# SimpleTimerPCB.net
KiCad netlist of a schematic drawn in EAGLE
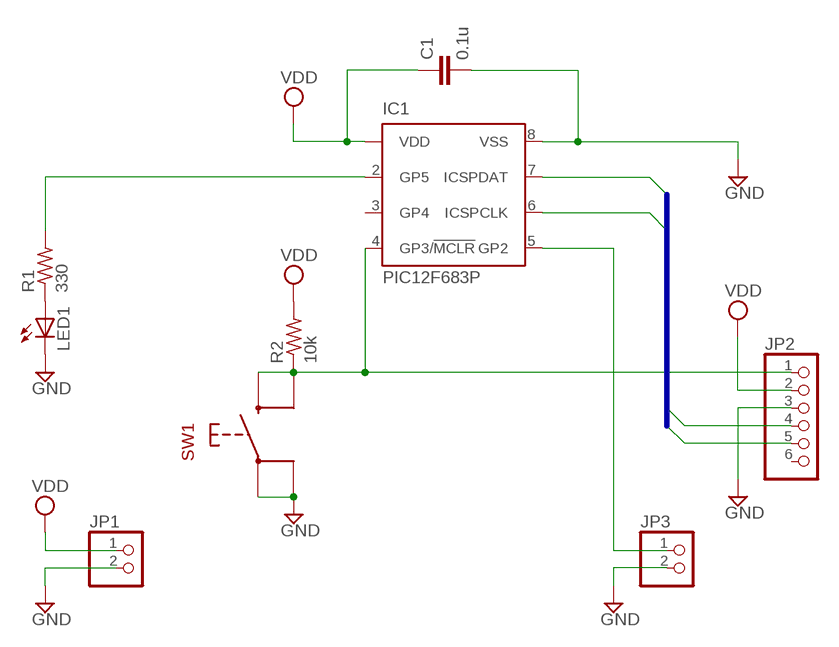
[diagram p0: schematic, sheet 1]

(export (version "E")
  (design (tool "Eeschema 10.0.6"))
  (components
    (comp (ref "C1")
      (value "0.1u")
      (footprint "eagle-import:C050-024X044")
      (libsource (lib "eagle-import") (part "C-EU050-024X044"))
    )
    (comp (ref "IC1")
      (value "PIC12F683P")
      (footprint "eagle-import:DIL8")
      (fields (field (name "MF") "MICROCHIP") (field (name "MPN") "PIC12F683-I/P"))
      (libsource (lib "eagle-import") (part "PIC12F683P"))
    )
    (comp (ref "JP1")
      (value "PINHD-1X2")
      (footprint "eagle-import:1X02")
      (libsource (lib "eagle-import") (part "PINHD-1X2"))
    )
    (comp (ref "JP2")
      (value "PINHD-1X6")
      (footprint "eagle-import:1X06")
      (libsource (lib "eagle-import") (part "PINHD-1X6"))
    )
    (comp (ref "JP3")
      (value "PINHD-1X2")
      (footprint "eagle-import:1X02")
      (libsource (lib "eagle-import") (part "PINHD-1X2"))
    )
    (comp (ref "LED1")
      (value "LED3MM")
      (footprint "eagle-import:LED3MM")
      (libsource (lib "eagle-import") (part "LED3MM"))
    )
    (comp (ref "R1")
      (value "330")
      (footprint "eagle-import:0204_7")
      (libsource (lib "eagle-import") (part "R-US_0204/7"))
    )
    (comp (ref "R2")
      (value "10k")
      (footprint "eagle-import:0204_7")
      (libsource (lib "eagle-import") (part "R-US_0204/7"))
    )
    (comp (ref "SW1")
      (value "TACT-SWITCH")
      (footprint "eagle-import:TACTSW-25X20")
      (libsource (lib "eagle-import") (part "TACT-SWITCH"))
    )
  )
  (nets
    (net (code "1") (name "/PIN4") (class "Default")
      (node (ref "IC1") (pin "7") (pinfunction "ICSPDAT_7") (pintype "bidirectional"))
      (node (ref "JP2") (pin "4") (pinfunction "4_4") (pintype "passive"))
    )
    (net (code "2") (name "/PIN5") (class "Default")
      (node (ref "IC1") (pin "6") (pinfunction "ICSPCLK_6") (pintype "bidirectional"))
      (node (ref "JP2") (pin "5") (pinfunction "5_5") (pintype "passive"))
    )
    (net (code "3") (name "GND") (class "Default")
      (node (ref "C1") (pin "2") (pinfunction "2_2") (pintype "passive"))
      (node (ref "IC1") (pin "8") (pinfunction "VSS_8") (pintype "power_in"))
      (node (ref "JP1") (pin "2") (pinfunction "2_2") (pintype "passive"))
      (node (ref "JP2") (pin "3") (pinfunction "3_3") (pintype "passive"))
      (node (ref "JP3") (pin "2") (pinfunction "2_2") (pintype "passive"))
      (node (ref "LED1") (pin "K") (pinfunction "C_K") (pintype "passive"))
      (node (ref "SW1") (pin "3") (pinfunction "P1_3") (pintype "passive"))
      (node (ref "SW1") (pin "4") (pinfunction "P2_4") (pintype "passive"))
    )
    (net (code "4") (name "Net-(IC1-GP2)") (class "Default")
      (node (ref "IC1") (pin "5") (pinfunction "GP2_5") (pintype "bidirectional"))
      (node (ref "JP3") (pin "1") (pinfunction "1_1") (pintype "passive"))
    )
    (net (code "5") (name "Net-(IC1-GP3{slash}~{MCLR})") (class "Default")
      (node (ref "IC1") (pin "4") (pinfunction "GP3/~{MCLR}_4") (pintype "bidirectional"))
      (node (ref "JP2") (pin "1") (pinfunction "1_1") (pintype "passive"))
      (node (ref "R2") (pin "1") (pinfunction "1_1") (pintype "passive"))
      (node (ref "SW1") (pin "1") (pinfunction "S1_1") (pintype "passive"))
      (node (ref "SW1") (pin "2") (pinfunction "S2_2") (pintype "passive"))
    )
    (net (code "6") (name "Net-(IC1-GP5)") (class "Default")
      (node (ref "IC1") (pin "2") (pinfunction "GP5_2") (pintype "bidirectional"))
      (node (ref "R1") (pin "2") (pinfunction "2_2") (pintype "passive"))
    )
    (net (code "7") (name "Net-(LED1-PadA)") (class "Default")
      (node (ref "LED1") (pin "A") (pinfunction "A_A") (pintype "passive"))
      (node (ref "R1") (pin "1") (pinfunction "1_1") (pintype "passive"))
    )
    (net (code "8") (name "VDD") (class "Default")
      (node (ref "C1") (pin "1") (pinfunction "1_1") (pintype "passive"))
      (node (ref "IC1") (pin "1") (pinfunction "VDD_1") (pintype "power_in"))
      (node (ref "JP1") (pin "1") (pinfunction "1_1") (pintype "passive"))
      (node (ref "JP2") (pin "2") (pinfunction "2_2") (pintype "passive"))
      (node (ref "R2") (pin "2") (pinfunction "2_2") (pintype "passive"))
    )
    (net (code "9") (name "unconnected-(IC1-GP4-Pad3)") (class "Default")
      (node (ref "IC1") (pin "3") (pinfunction "GP4_3") (pintype "bidirectional"))
    )
    (net (code "10") (name "unconnected-(JP2-Pad6)") (class "Default")
      (node (ref "JP2") (pin "6") (pinfunction "6_6") (pintype "passive"))
    )
  )
)
